# main.net
KiCad netlist of a schematic drawn in Altium Designer
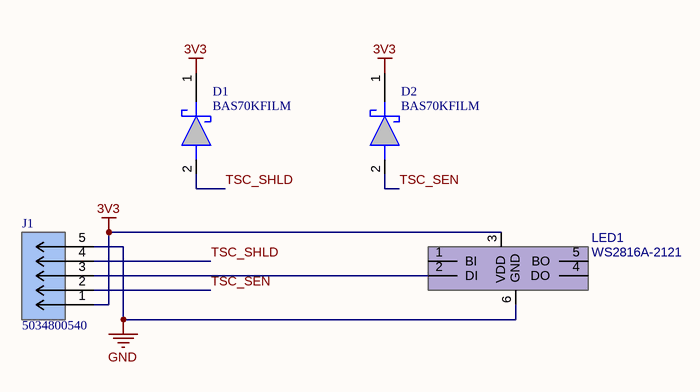
[diagram p0: main.SchDoc]

(export (version "E")
  (design (tool "Eeschema 10.0.6"))
  (components
    (comp (ref "D1")
      (value "BAS70KFILM")
      (footprint "SODFL1608X70N")
      (description "STMicroelectronics BAS70KFILM, SMT Schottky Diode, 70V 70mA, 2-Pin SOD-523")
      (fields (field (name "MOUSER PART NUMBER") "511-BAS70KFILM"))
      (libsource (lib "BAS70KFILM") (part "BAS70KFILM"))
    )
    (comp (ref "D2")
      (value "BAS70KFILM")
      (footprint "SODFL1608X70N")
      (description "STMicroelectronics BAS70KFILM, SMT Schottky Diode, 70V 70mA, 2-Pin SOD-523")
      (fields (field (name "MOUSER PART NUMBER") "511-BAS70KFILM"))
      (libsource (lib "BAS70KFILM") (part "BAS70KFILM"))
    )
    (comp (ref "J1")
      (value "5034800540")
      (footprint "CONN_503480-0540_MOL")
      (fields (field (name "COPYRIGHT") "Copyright (C) 2025 Ultra Librarian. All rights reserved."))
      (libsource (lib "5034800540") (part "5034800540"))
    )
    (comp (ref "LED1")
      (value "WS2816A-2121")
      (footprint "ws2816a-2121")
      (libsource (lib "ws2816a-2121") (part "WS2816A-2121"))
    )
  )
  (nets
    (net (code "1") (name "/TSC_SEN") (class "Default")
      (node (ref "D2") (pin "2") (pinfunction "A_2") (pintype "passive"))
      (node (ref "J1") (pin "2") (pinfunction "2_2") (pintype "passive"))
    )
    (net (code "2") (name "/TSC_SHLD") (class "Default")
      (node (ref "D1") (pin "2") (pinfunction "A_2") (pintype "passive"))
      (node (ref "J1") (pin "4") (pinfunction "4_4") (pintype "passive"))
    )
    (net (code "3") (name "3V3") (class "Default")
      (node (ref "D1") (pin "1") (pinfunction "K_1") (pintype "passive"))
      (node (ref "D2") (pin "1") (pinfunction "K_1") (pintype "passive"))
      (node (ref "J1") (pin "1") (pinfunction "1_1") (pintype "passive"))
      (node (ref "LED1") (pin "3") (pinfunction "VDD_3") (pintype "passive"))
    )
    (net (code "4") (name "GND") (class "Default")
      (node (ref "J1") (pin "5") (pinfunction "5_5") (pintype "passive"))
      (node (ref "LED1") (pin "6") (pinfunction "GND_6") (pintype "passive"))
    )
    (net (code "5") (name "Net-(LED1-DI)") (class "Default")
      (node (ref "J1") (pin "3") (pinfunction "3_3") (pintype "passive"))
      (node (ref "LED1") (pin "2") (pinfunction "DI_2") (pintype "passive"))
    )
    (net (code "6") (name "unconnected-(LED1-BI-Pad1)") (class "Default")
      (node (ref "LED1") (pin "1") (pinfunction "BI_1") (pintype "passive"))
    )
    (net (code "7") (name "unconnected-(LED1-BO-Pad5)") (class "Default")
      (node (ref "LED1") (pin "5") (pinfunction "BO_5") (pintype "passive"))
    )
    (net (code "8") (name "unconnected-(LED1-DO-Pad4)") (class "Default")
      (node (ref "LED1") (pin "4") (pinfunction "DO_4") (pintype "passive"))
    )
  )
)
